# rc6551z80_v3.net
KiCad netlist of a schematic drawn in EAGLE
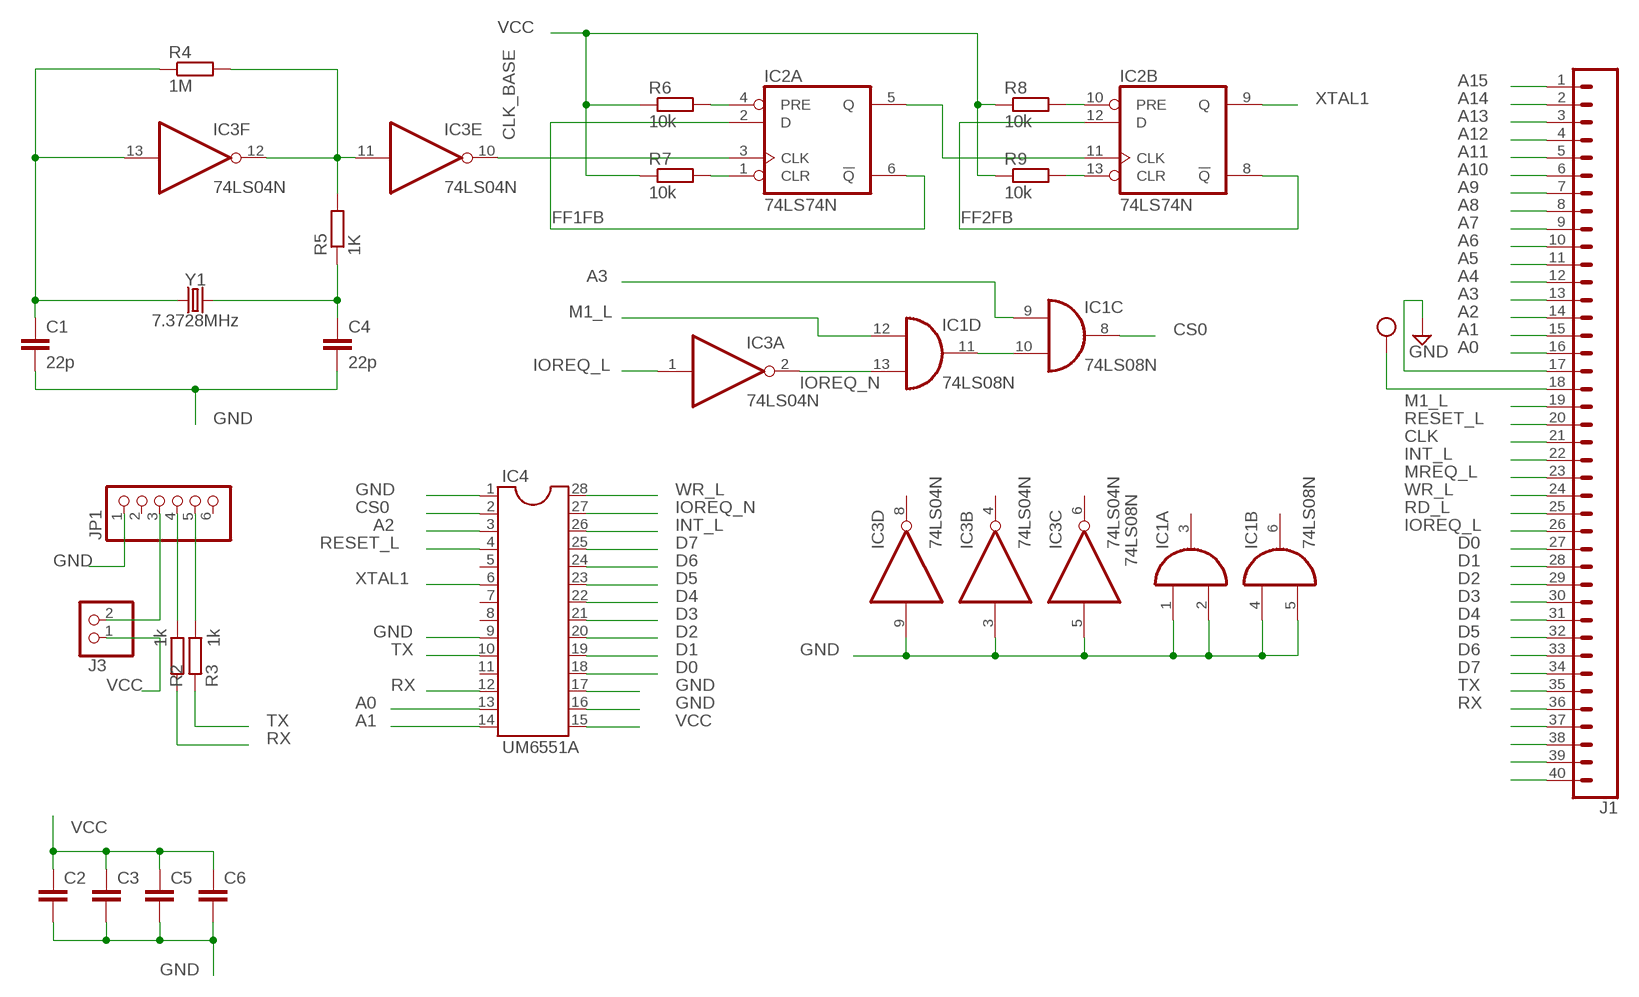
[diagram p0: schematic, sheet 1]

(export (version "E")
  (design (tool "Eeschema 10.0.6"))
  (components
    (comp (ref "C1")
      (value "22p")
      (footprint "eagle-import:C025-024X044")
      (libsource (lib "eagle-import") (part "rcl_334_C-EU025-024X044"))
    )
    (comp (ref "C2")
      (value "C-EU050-025X075")
      (footprint "eagle-import:C050-025X075")
      (libsource (lib "eagle-import") (part "C-EU050-025X075"))
    )
    (comp (ref "C3")
      (value "C-EU050-025X075")
      (footprint "eagle-import:C050-025X075")
      (libsource (lib "eagle-import") (part "C-EU050-025X075"))
    )
    (comp (ref "C4")
      (value "22p")
      (footprint "eagle-import:C025-024X044")
      (libsource (lib "eagle-import") (part "rcl_334_C-EU025-024X044"))
    )
    (comp (ref "C5")
      (value "C-EU050-025X075")
      (footprint "eagle-import:C050-025X075")
      (libsource (lib "eagle-import") (part "C-EU050-025X075"))
    )
    (comp (ref "C6")
      (value "C-EU050-025X075")
      (footprint "eagle-import:C050-025X075")
      (libsource (lib "eagle-import") (part "C-EU050-025X075"))
    )
    (comp (ref "IC1")
      (value "74LS08N")
      (footprint "eagle-import:DIL14")
      (libsource (lib "eagle-import") (part "7408NLS"))
    )
    (comp (ref "IC2")
      (value "74LS74N")
      (footprint "eagle-import:DIL14")
      (libsource (lib "eagle-import") (part "7474NLS"))
    )
    (comp (ref "IC3")
      (value "74LS04N")
      (footprint "eagle-import:DIL14")
      (libsource (lib "eagle-import") (part "7404NLS"))
    )
    (comp (ref "IC4")
      (value "UM6551A")
      (footprint "eagle-import:DIL28-6")
      (libsource (lib "eagle-import") (part "DIL28"))
    )
    (comp (ref "J1")
      (value "CONN_40OFFSET")
      (footprint "eagle-import:1X40_OFFSET")
      (libsource (lib "eagle-import") (part "CONN_40OFFSET"))
    )
    (comp (ref "J3")
      (value "PINHD-1X2")
      (footprint "eagle-import:1X02")
      (libsource (lib "eagle-import") (part "PINHD-1X2"))
    )
    (comp (ref "JP1")
      (value "PINHD-1X6")
      (footprint "eagle-import:1X06")
      (libsource (lib "eagle-import") (part "PINHD-1X6"))
    )
    (comp (ref "R2")
      (value "1k")
      (footprint "eagle-import:0204_7")
      (libsource (lib "eagle-import") (part "R-EU_0204/7"))
    )
    (comp (ref "R3")
      (value "1k")
      (footprint "eagle-import:0204_7")
      (libsource (lib "eagle-import") (part "R-EU_0204/7"))
    )
    (comp (ref "R4")
      (value "1M")
      (footprint "eagle-import:0204_7")
      (libsource (lib "eagle-import") (part "R-EU_0204/7"))
    )
    (comp (ref "R5")
      (value "1K")
      (footprint "eagle-import:0204_7")
      (libsource (lib "eagle-import") (part "R-EU_0204/7"))
    )
    (comp (ref "R6")
      (value "10k")
      (footprint "eagle-import:0204_7")
      (libsource (lib "eagle-import") (part "R-EU_0204/7"))
    )
    (comp (ref "R7")
      (value "10k")
      (footprint "eagle-import:0204_7")
      (libsource (lib "eagle-import") (part "R-EU_0204/7"))
    )
    (comp (ref "R8")
      (value "10k")
      (footprint "eagle-import:0204_7")
      (libsource (lib "eagle-import") (part "R-EU_0204/7"))
    )
    (comp (ref "R9")
      (value "10k")
      (footprint "eagle-import:0204_7")
      (libsource (lib "eagle-import") (part "R-EU_0204/7"))
    )
    (comp (ref "Y1")
      (value "7.3728MHz")
      (footprint "eagle-import:HC49U")
      (libsource (lib "eagle-import") (part "CRYSTALPTH-HC49UV"))
    )
  )
  (nets
    (net (code "1") (name "/A0") (class "Default")
      (node (ref "IC4") (pin "13") (pinfunction "13_13") (pintype "passive"))
      (node (ref "J1") (pin "16") (pinfunction "16_16") (pintype "passive"))
    )
    (net (code "2") (name "/A1") (class "Default")
      (node (ref "IC4") (pin "14") (pinfunction "14_14") (pintype "passive"))
      (node (ref "J1") (pin "15") (pinfunction "15_15") (pintype "passive"))
    )
    (net (code "3") (name "/A2") (class "Default")
      (node (ref "IC4") (pin "3") (pinfunction "3_3") (pintype "passive"))
      (node (ref "J1") (pin "14") (pinfunction "14_14") (pintype "passive"))
    )
    (net (code "4") (name "/A3") (class "Default")
      (node (ref "IC1") (pin "9") (pinfunction "I0_9") (pintype "input"))
      (node (ref "J1") (pin "13") (pinfunction "13_13") (pintype "passive"))
    )
    (net (code "5") (name "/A4") (class "Default")
      (node (ref "J1") (pin "12") (pinfunction "12_12") (pintype "passive"))
    )
    (net (code "6") (name "/A5") (class "Default")
      (node (ref "J1") (pin "11") (pinfunction "11_11") (pintype "passive"))
    )
    (net (code "7") (name "/A6") (class "Default")
      (node (ref "J1") (pin "10") (pinfunction "10_10") (pintype "passive"))
    )
    (net (code "8") (name "/A7") (class "Default")
      (node (ref "J1") (pin "9") (pinfunction "9_9") (pintype "passive"))
    )
    (net (code "9") (name "/A8") (class "Default")
      (node (ref "J1") (pin "8") (pinfunction "8_8") (pintype "passive"))
    )
    (net (code "10") (name "/A9") (class "Default")
      (node (ref "J1") (pin "7") (pinfunction "7_7") (pintype "passive"))
    )
    (net (code "11") (name "/A10") (class "Default")
      (node (ref "J1") (pin "6") (pinfunction "6_6") (pintype "passive"))
    )
    (net (code "12") (name "/A11") (class "Default")
      (node (ref "J1") (pin "5") (pinfunction "5_5") (pintype "passive"))
    )
    (net (code "13") (name "/A12") (class "Default")
      (node (ref "J1") (pin "4") (pinfunction "4_4") (pintype "passive"))
    )
    (net (code "14") (name "/A13") (class "Default")
      (node (ref "J1") (pin "3") (pinfunction "3_3") (pintype "passive"))
    )
    (net (code "15") (name "/A14") (class "Default")
      (node (ref "J1") (pin "2") (pinfunction "2_2") (pintype "passive"))
    )
    (net (code "16") (name "/A15") (class "Default")
      (node (ref "J1") (pin "1") (pinfunction "1_1") (pintype "passive"))
    )
    (net (code "17") (name "/CLK") (class "Default")
      (node (ref "J1") (pin "21") (pinfunction "21_21") (pintype "passive"))
    )
    (net (code "18") (name "/CLK_BASE") (class "Default")
      (node (ref "IC2") (pin "3") (pinfunction "CLK_3") (pintype "input"))
      (node (ref "IC3") (pin "10") (pinfunction "O_10") (pintype "output"))
    )
    (net (code "19") (name "/CS0") (class "Default")
      (node (ref "IC1") (pin "8") (pinfunction "O_8") (pintype "output"))
      (node (ref "IC4") (pin "2") (pinfunction "2_2") (pintype "passive"))
    )
    (net (code "20") (name "/D0") (class "Default")
      (node (ref "IC4") (pin "18") (pinfunction "18_18") (pintype "passive"))
      (node (ref "J1") (pin "27") (pinfunction "27_27") (pintype "passive"))
    )
    (net (code "21") (name "/D1") (class "Default")
      (node (ref "IC4") (pin "19") (pinfunction "19_19") (pintype "passive"))
      (node (ref "J1") (pin "28") (pinfunction "28_28") (pintype "passive"))
    )
    (net (code "22") (name "/D2") (class "Default")
      (node (ref "IC4") (pin "20") (pinfunction "20_20") (pintype "passive"))
      (node (ref "J1") (pin "29") (pinfunction "29_29") (pintype "passive"))
    )
    (net (code "23") (name "/D3") (class "Default")
      (node (ref "IC4") (pin "21") (pinfunction "21_21") (pintype "passive"))
      (node (ref "J1") (pin "30") (pinfunction "30_30") (pintype "passive"))
    )
    (net (code "24") (name "/D4") (class "Default")
      (node (ref "IC4") (pin "22") (pinfunction "22_22") (pintype "passive"))
      (node (ref "J1") (pin "31") (pinfunction "31_31") (pintype "passive"))
    )
    (net (code "25") (name "/D5") (class "Default")
      (node (ref "IC4") (pin "23") (pinfunction "23_23") (pintype "passive"))
      (node (ref "J1") (pin "32") (pinfunction "32_32") (pintype "passive"))
    )
    (net (code "26") (name "/D6") (class "Default")
      (node (ref "IC4") (pin "24") (pinfunction "24_24") (pintype "passive"))
      (node (ref "J1") (pin "33") (pinfunction "33_33") (pintype "passive"))
    )
    (net (code "27") (name "/D7") (class "Default")
      (node (ref "IC4") (pin "25") (pinfunction "25_25") (pintype "passive"))
      (node (ref "J1") (pin "34") (pinfunction "34_34") (pintype "passive"))
    )
    (net (code "28") (name "/FF1FB") (class "Default")
      (node (ref "IC2") (pin "2") (pinfunction "D_2") (pintype "input"))
      (node (ref "IC2") (pin "6") (pinfunction "~{Q}_6") (pintype "output"))
    )
    (net (code "29") (name "/FF2FB") (class "Default")
      (node (ref "IC2") (pin "12") (pinfunction "D_12") (pintype "input"))
      (node (ref "IC2") (pin "8") (pinfunction "~{Q}_8") (pintype "output"))
    )
    (net (code "30") (name "/INT_L") (class "Default")
      (node (ref "IC4") (pin "26") (pinfunction "26_26") (pintype "passive"))
      (node (ref "J1") (pin "22") (pinfunction "22_22") (pintype "passive"))
    )
    (net (code "31") (name "/IOREQ_L") (class "Default")
      (node (ref "IC3") (pin "1") (pinfunction "I_1") (pintype "input"))
      (node (ref "J1") (pin "26") (pinfunction "26_26") (pintype "passive"))
    )
    (net (code "32") (name "/IOREQ_N") (class "Default")
      (node (ref "IC1") (pin "13") (pinfunction "I1_13") (pintype "input"))
      (node (ref "IC3") (pin "2") (pinfunction "O_2") (pintype "output"))
      (node (ref "IC4") (pin "27") (pinfunction "27_27") (pintype "passive"))
    )
    (net (code "33") (name "/M1_L") (class "Default")
      (node (ref "IC1") (pin "12") (pinfunction "I0_12") (pintype "input"))
      (node (ref "J1") (pin "19") (pinfunction "19_19") (pintype "passive"))
    )
    (net (code "34") (name "/MREQ_L") (class "Default")
      (node (ref "J1") (pin "23") (pinfunction "23_23") (pintype "passive"))
    )
    (net (code "35") (name "/RD_L") (class "Default")
      (node (ref "J1") (pin "25") (pinfunction "25_25") (pintype "passive"))
    )
    (net (code "36") (name "/RESET_L") (class "Default")
      (node (ref "IC4") (pin "4") (pinfunction "4_4") (pintype "passive"))
      (node (ref "J1") (pin "20") (pinfunction "20_20") (pintype "passive"))
    )
    (net (code "37") (name "/RX") (class "Default")
      (node (ref "IC4") (pin "12") (pinfunction "12_12") (pintype "passive"))
      (node (ref "J1") (pin "36") (pinfunction "36_36") (pintype "passive"))
      (node (ref "R2") (pin "2") (pinfunction "2_2") (pintype "passive"))
    )
    (net (code "38") (name "/TX") (class "Default")
      (node (ref "IC4") (pin "10") (pinfunction "10_10") (pintype "passive"))
      (node (ref "J1") (pin "35") (pinfunction "35_35") (pintype "passive"))
      (node (ref "R3") (pin "2") (pinfunction "2_2") (pintype "passive"))
    )
    (net (code "39") (name "/WR_L") (class "Default")
      (node (ref "IC4") (pin "28") (pinfunction "28_28") (pintype "passive"))
      (node (ref "J1") (pin "24") (pinfunction "24_24") (pintype "passive"))
    )
    (net (code "40") (name "/XTAL1") (class "Default")
      (node (ref "IC2") (pin "9") (pinfunction "Q_9") (pintype "output"))
      (node (ref "IC4") (pin "6") (pinfunction "6_6") (pintype "passive"))
    )
    (net (code "41") (name "GND") (class "Default")
      (node (ref "C1") (pin "2") (pinfunction "2_2") (pintype "passive"))
      (node (ref "C2") (pin "2") (pinfunction "2_2") (pintype "passive"))
      (node (ref "C3") (pin "2") (pinfunction "2_2") (pintype "passive"))
      (node (ref "C4") (pin "2") (pinfunction "2_2") (pintype "passive"))
      (node (ref "C5") (pin "2") (pinfunction "2_2") (pintype "passive"))
      (node (ref "C6") (pin "2") (pinfunction "2_2") (pintype "passive"))
      (node (ref "IC1") (pin "1") (pinfunction "I0_1") (pintype "input"))
      (node (ref "IC1") (pin "2") (pinfunction "I1_2") (pintype "input"))
      (node (ref "IC1") (pin "4") (pinfunction "I0_4") (pintype "input"))
      (node (ref "IC1") (pin "5") (pinfunction "I1_5") (pintype "input"))
      (node (ref "IC3") (pin "3") (pinfunction "I_3") (pintype "input"))
      (node (ref "IC3") (pin "5") (pinfunction "I_5") (pintype "input"))
      (node (ref "IC3") (pin "9") (pinfunction "I_9") (pintype "input"))
      (node (ref "IC4") (pin "1") (pinfunction "1_1") (pintype "passive"))
      (node (ref "IC4") (pin "16") (pinfunction "16_16") (pintype "passive"))
      (node (ref "IC4") (pin "17") (pinfunction "17_17") (pintype "passive"))
      (node (ref "IC4") (pin "9") (pinfunction "9_9") (pintype "passive"))
      (node (ref "J1") (pin "17") (pinfunction "17_17") (pintype "passive"))
      (node (ref "JP1") (pin "1") (pinfunction "1_1") (pintype "passive"))
    )
    (net (code "42") (name "Net-(C4-Pad1)") (class "Default")
      (node (ref "C4") (pin "1") (pinfunction "1_1") (pintype "passive"))
      (node (ref "R5") (pin "1") (pinfunction "1_1") (pintype "passive"))
      (node (ref "Y1") (pin "2") (pinfunction "2_2") (pintype "passive"))
    )
    (net (code "43") (name "Net-(IC1C-I1)") (class "Default")
      (node (ref "IC1") (pin "10") (pinfunction "I1_10") (pintype "input"))
      (node (ref "IC1") (pin "11") (pinfunction "O_11") (pintype "output"))
    )
    (net (code "44") (name "Net-(IC2A-CLR)") (class "Default")
      (node (ref "IC2") (pin "1") (pinfunction "CLR_1") (pintype "input"))
      (node (ref "R7") (pin "2") (pinfunction "2_2") (pintype "passive"))
    )
    (net (code "45") (name "Net-(IC2A-PRE)") (class "Default")
      (node (ref "IC2") (pin "4") (pinfunction "PRE_4") (pintype "input"))
      (node (ref "R6") (pin "2") (pinfunction "2_2") (pintype "passive"))
    )
    (net (code "46") (name "Net-(IC2A-Q)") (class "Default")
      (node (ref "IC2") (pin "11") (pinfunction "CLK_11") (pintype "input"))
      (node (ref "IC2") (pin "5") (pinfunction "Q_5") (pintype "output"))
    )
    (net (code "47") (name "Net-(IC2B-CLR)") (class "Default")
      (node (ref "IC2") (pin "13") (pinfunction "CLR_13") (pintype "input"))
      (node (ref "R9") (pin "2") (pinfunction "2_2") (pintype "passive"))
    )
    (net (code "48") (name "Net-(IC2B-PRE)") (class "Default")
      (node (ref "IC2") (pin "10") (pinfunction "PRE_10") (pintype "input"))
      (node (ref "R8") (pin "2") (pinfunction "2_2") (pintype "passive"))
    )
    (net (code "49") (name "Net-(IC3E-I)") (class "Default")
      (node (ref "IC3") (pin "11") (pinfunction "I_11") (pintype "input"))
      (node (ref "IC3") (pin "12") (pinfunction "O_12") (pintype "output"))
      (node (ref "R4") (pin "2") (pinfunction "2_2") (pintype "passive"))
      (node (ref "R5") (pin "2") (pinfunction "2_2") (pintype "passive"))
    )
    (net (code "50") (name "Net-(IC3F-I)") (class "Default")
      (node (ref "C1") (pin "1") (pinfunction "1_1") (pintype "passive"))
      (node (ref "IC3") (pin "13") (pinfunction "I_13") (pintype "input"))
      (node (ref "R4") (pin "1") (pinfunction "1_1") (pintype "passive"))
      (node (ref "Y1") (pin "1") (pinfunction "1_1") (pintype "passive"))
    )
    (net (code "51") (name "Net-(J3-Pad2)") (class "Default")
      (node (ref "J3") (pin "2") (pinfunction "2_2") (pintype "passive"))
      (node (ref "JP1") (pin "3") (pinfunction "3_3") (pintype "passive"))
    )
    (net (code "52") (name "Net-(JP1-Pad4)") (class "Default")
      (node (ref "JP1") (pin "4") (pinfunction "4_4") (pintype "passive"))
      (node (ref "R2") (pin "1") (pinfunction "1_1") (pintype "passive"))
    )
    (net (code "53") (name "Net-(JP1-Pad5)") (class "Default")
      (node (ref "JP1") (pin "5") (pinfunction "5_5") (pintype "passive"))
      (node (ref "R3") (pin "1") (pinfunction "1_1") (pintype "passive"))
    )
    (net (code "54") (name "VCC") (class "Default")
      (node (ref "C2") (pin "1") (pinfunction "1_1") (pintype "passive"))
      (node (ref "C3") (pin "1") (pinfunction "1_1") (pintype "passive"))
      (node (ref "C5") (pin "1") (pinfunction "1_1") (pintype "passive"))
      (node (ref "C6") (pin "1") (pinfunction "1_1") (pintype "passive"))
      (node (ref "IC4") (pin "15") (pinfunction "15_15") (pintype "passive"))
      (node (ref "J1") (pin "18") (pinfunction "18_18") (pintype "passive"))
      (node (ref "J3") (pin "1") (pinfunction "1_1") (pintype "passive"))
      (node (ref "R6") (pin "1") (pinfunction "1_1") (pintype "passive"))
      (node (ref "R7") (pin "1") (pinfunction "1_1") (pintype "passive"))
      (node (ref "R8") (pin "1") (pinfunction "1_1") (pintype "passive"))
      (node (ref "R9") (pin "1") (pinfunction "1_1") (pintype "passive"))
    )
    (net (code "55") (name "unconnected-(IC1A-O-Pad3)") (class "Default")
      (node (ref "IC1") (pin "3") (pinfunction "O_3") (pintype "output"))
    )
    (net (code "56") (name "unconnected-(IC1B-O-Pad6)") (class "Default")
      (node (ref "IC1") (pin "6") (pinfunction "O_6") (pintype "output"))
    )
    (net (code "57") (name "unconnected-(IC3B-O-Pad4)") (class "Default")
      (node (ref "IC3") (pin "4") (pinfunction "O_4") (pintype "output"))
    )
    (net (code "58") (name "unconnected-(IC3C-O-Pad6)") (class "Default")
      (node (ref "IC3") (pin "6") (pinfunction "O_6") (pintype "output"))
    )
    (net (code "59") (name "unconnected-(IC3D-O-Pad8)") (class "Default")
      (node (ref "IC3") (pin "8") (pinfunction "O_8") (pintype "output"))
    )
    (net (code "60") (name "unconnected-(IC4-Pad5)") (class "Default")
      (node (ref "IC4") (pin "5") (pinfunction "5_5") (pintype "passive"))
    )
    (net (code "61") (name "unconnected-(IC4-Pad7)") (class "Default")
      (node (ref "IC4") (pin "7") (pinfunction "7_7") (pintype "passive"))
    )
    (net (code "62") (name "unconnected-(IC4-Pad8)") (class "Default")
      (node (ref "IC4") (pin "8") (pinfunction "8_8") (pintype "passive"))
    )
    (net (code "63") (name "unconnected-(IC4-Pad11)") (class "Default")
      (node (ref "IC4") (pin "11") (pinfunction "11_11") (pintype "passive"))
    )
    (net (code "64") (name "unconnected-(J1-Pad37)") (class "Default")
      (node (ref "J1") (pin "37") (pinfunction "37_37") (pintype "passive"))
    )
    (net (code "65") (name "unconnected-(J1-Pad38)") (class "Default")
      (node (ref "J1") (pin "38") (pinfunction "38_38") (pintype "passive"))
    )
    (net (code "66") (name "unconnected-(J1-Pad39)") (class "Default")
      (node (ref "J1") (pin "39") (pinfunction "39_39") (pintype "passive"))
    )
    (net (code "67") (name "unconnected-(J1-Pad40)") (class "Default")
      (node (ref "J1") (pin "40") (pinfunction "40_40") (pintype "passive"))
    )
    (net (code "68") (name "unconnected-(JP1-Pad2)") (class "Default")
      (node (ref "JP1") (pin "2") (pinfunction "2_2") (pintype "passive"))
    )
    (net (code "69") (name "unconnected-(JP1-Pad6)") (class "Default")
      (node (ref "JP1") (pin "6") (pinfunction "6_6") (pintype "passive"))
    )
  )
)
